# WalkMod_A0.net
KiCad netlist of a schematic drawn in Altium Designer
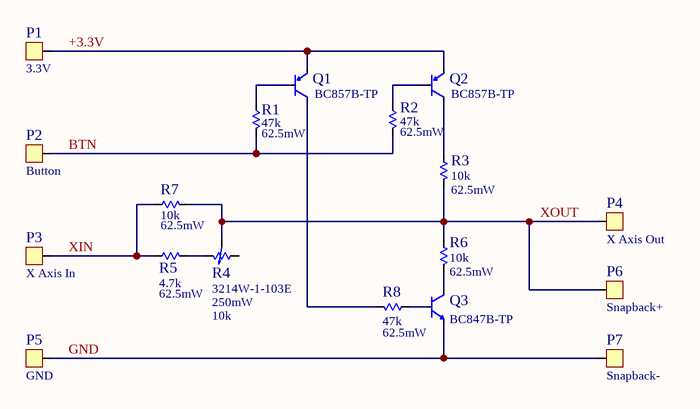
[diagram p0: WalkMod A0.SchDoc]

(export (version "E")
  (design (tool "Eeschema 10.0.6"))
  (components
    (comp (ref "P1")
      (value "SMD Pad 1 pin")
      (footprint "PAD_2X1.5_SQUARE")
      (description "Single SMD Pad")
      (fields (field (name "NAME") "3.3V"))
      (libsource (lib "WalkMod") (part "SMD Pad 1 pin"))
    )
    (comp (ref "P2")
      (value "SMD Pad 1 pin")
      (footprint "PAD_2X1.5_SQUARE")
      (description "Single SMD Pad")
      (fields (field (name "NAME") "Button"))
      (libsource (lib "WalkMod") (part "SMD Pad 1 pin"))
    )
    (comp (ref "P3")
      (value "SMD Pad 1 pin")
      (footprint "PAD_2X1.5_SQUARE")
      (description "Single SMD Pad")
      (fields (field (name "NAME") "X Axis In"))
      (libsource (lib "WalkMod") (part "SMD Pad 1 pin"))
    )
    (comp (ref "P4")
      (value "SMD Pad 1 pin")
      (footprint "PAD_2X1.5_SQUARE")
      (description "Single SMD Pad")
      (fields (field (name "NAME") "X Axis Out"))
      (libsource (lib "") (part "SMD Pad 1 pin_1"))
    )
    (comp (ref "P5")
      (value "SMD Pad 1 pin")
      (footprint "PAD_2X1.5_SQUARE")
      (description "Single SMD Pad")
      (fields (field (name "NAME") "GND"))
      (libsource (lib "WalkMod") (part "SMD Pad 1 pin"))
    )
    (comp (ref "P6")
      (value "SMD Pad 1 pin")
      (footprint "PAD_1.8X0.95_SQUARE")
      (description "Single SMD Pad")
      (fields (field (name "NAME") "Snapback+"))
      (libsource (lib "") (part "SMD Pad 1 pin_1"))
    )
    (comp (ref "P7")
      (value "SMD Pad 1 pin")
      (footprint "PAD_1.8X0.95_SQUARE")
      (description "Single SMD Pad")
      (fields (field (name "NAME") "Snapback-"))
      (libsource (lib "") (part "SMD Pad 1 pin_1"))
    )
    (comp (ref "Q1")
      (value "BC857B-TP")
      (footprint "BC8xx_SOT23-3_C")
      (description "Bipolar (BJT) Transistor PNP 45 V 100 mA 200MHz 310 mW Surface Mount SOT-23")
      (libsource (lib "WalkMod") (part "BC857B-TP"))
    )
    (comp (ref "Q2")
      (value "BC857B-TP")
      (footprint "BC8xx_SOT23-3_C")
      (description "Bipolar (BJT) Transistor PNP 45 V 100 mA 200MHz 310 mW Surface Mount SOT-23")
      (libsource (lib "WalkMod") (part "BC857B-TP"))
    )
    (comp (ref "Q3")
      (value "BC847B-TP")
      (footprint "BC8xx_SOT23-3_C")
      (description "Bipolar (BJT) Transistor NPN 45 V 100 mA 100MHz 225 mW Surface Mount SOT-23")
      (libsource (lib "WalkMod") (part "BC847B-TP"))
    )
    (comp (ref "R1")
      (value "47k")
      (footprint "RT0402_C")
      (description "47 kOhms ±0.5% 0.063W, 1/16W Chip Resistor 0402 (1005 Metric) - Thin Film")
      (fields (field (name "VALUE2") "62.5mW") (field (name "Comment") "RT0402DRD0747KL"))
      (libsource (lib "WalkMod") (part "RT0402DRD0747KL"))
    )
    (comp (ref "R2")
      (value "47k")
      (footprint "RT0402_C")
      (description "47 kOhms ±0.5% 0.063W, 1/16W Chip Resistor 0402 (1005 Metric) - Thin Film")
      (fields (field (name "VALUE2") "62.5mW") (field (name "Comment") "RT0402DRD0747KL"))
      (libsource (lib "WalkMod") (part "RT0402DRD0747KL"))
    )
    (comp (ref "R3")
      (value "10k")
      (footprint "AT0402_C")
      (fields (field (name "VALUE2") "62.5mW") (field (name "Comment") "AT0402FRE0710KL"))
      (libsource (lib "WalkMod") (part "AT0402FRE0710KL"))
    )
    (comp (ref "R4")
      (value "3214W-1-103E")
      (footprint "BOURNS_3214W_C")
      (description "10 kOhms 0.25W, 1/4W J Lead Surface Mount Trimmer Potentiometer Cermet 5.0 Turn Top Adjustment")
      (fields (field (name "VALUE2") "250mW") (field (name "ALTIUM_VALUE") "10k"))
      (libsource (lib "WalkMod") (part "3214W-1-103E"))
    )
    (comp (ref "R5")
      (value "4.7k")
      (footprint "RT0402_C")
      (description "4.7 kOhms ±1% 0.063W, 1/16W Chip Resistor 0402 (1005 Metric) - Thin Film")
      (fields (field (name "VALUE2") "62.5mW") (field (name "Comment") "RT0402FRE074K7L"))
      (libsource (lib "WalkMod") (part "RT0402FRE074K7L"))
    )
    (comp (ref "R6")
      (value "10k")
      (footprint "AT0402_C")
      (fields (field (name "VALUE2") "62.5mW") (field (name "Comment") "AT0402FRE0710KL"))
      (libsource (lib "WalkMod") (part "AT0402FRE0710KL"))
    )
    (comp (ref "R7")
      (value "10k")
      (footprint "AT0402_C")
      (fields (field (name "VALUE2") "62.5mW") (field (name "Comment") "AT0402FRE0710KL"))
      (libsource (lib "WalkMod") (part "AT0402FRE0710KL"))
    )
    (comp (ref "R8")
      (value "47k")
      (footprint "RT0402_C")
      (description "47 kOhms ±0.5% 0.063W, 1/16W Chip Resistor 0402 (1005 Metric) - Thin Film")
      (fields (field (name "VALUE2") "62.5mW") (field (name "Comment") "RT0402DRD0747KL"))
      (libsource (lib "WalkMod") (part "RT0402DRD0747KL"))
    )
  )
  (nets
    (net (code "1") (name "/+3.3V") (class "Default")
      (node (ref "P1") (pin "1") (pinfunction "1_1") (pintype "passive"))
      (node (ref "Q1") (pin "E") (pinfunction "E_E") (pintype "passive"))
      (node (ref "Q2") (pin "E") (pinfunction "E_E") (pintype "passive"))
    )
    (net (code "2") (name "/BTN") (class "Default")
      (node (ref "P2") (pin "1") (pinfunction "1_1") (pintype "passive"))
      (node (ref "R1") (pin "1") (pinfunction "1_1") (pintype "passive"))
      (node (ref "R2") (pin "1") (pinfunction "1_1") (pintype "passive"))
    )
    (net (code "3") (name "/GND") (class "Default")
      (node (ref "P5") (pin "1") (pinfunction "1_1") (pintype "passive"))
      (node (ref "P7") (pin "1") (pinfunction "1_1") (pintype "passive"))
      (node (ref "Q3") (pin "E") (pinfunction "E_E") (pintype "passive"))
    )
    (net (code "4") (name "/XIN") (class "Default")
      (node (ref "P3") (pin "1") (pinfunction "1_1") (pintype "passive"))
      (node (ref "R5") (pin "1") (pinfunction "1_1") (pintype "passive"))
      (node (ref "R7") (pin "2") (pinfunction "2_2") (pintype "passive"))
    )
    (net (code "5") (name "/XOUT") (class "Default")
      (node (ref "P4") (pin "1") (pinfunction "1_1") (pintype "passive"))
      (node (ref "P6") (pin "1") (pinfunction "1_1") (pintype "passive"))
      (node (ref "R3") (pin "2") (pinfunction "2_2") (pintype "passive"))
      (node (ref "R4") (pin "2") (pinfunction "2_2") (pintype "passive"))
      (node (ref "R6") (pin "1") (pinfunction "1_1") (pintype "passive"))
      (node (ref "R7") (pin "1") (pinfunction "1_1") (pintype "passive"))
    )
    (net (code "6") (name "Net-(Q1-PadB)") (class "Default")
      (node (ref "Q1") (pin "B") (pinfunction "B_B") (pintype "passive"))
      (node (ref "R1") (pin "2") (pinfunction "2_2") (pintype "passive"))
    )
    (net (code "7") (name "Net-(Q1-PadC)") (class "Default")
      (node (ref "Q1") (pin "C") (pinfunction "C_C") (pintype "passive"))
      (node (ref "R8") (pin "1") (pinfunction "1_1") (pintype "passive"))
    )
    (net (code "8") (name "Net-(Q2-PadB)") (class "Default")
      (node (ref "Q2") (pin "B") (pinfunction "B_B") (pintype "passive"))
      (node (ref "R2") (pin "2") (pinfunction "2_2") (pintype "passive"))
    )
    (net (code "9") (name "Net-(Q2-PadC)") (class "Default")
      (node (ref "Q2") (pin "C") (pinfunction "C_C") (pintype "passive"))
      (node (ref "R3") (pin "1") (pinfunction "1_1") (pintype "passive"))
    )
    (net (code "10") (name "Net-(Q3-PadB)") (class "Default")
      (node (ref "Q3") (pin "B") (pinfunction "B_B") (pintype "passive"))
      (node (ref "R8") (pin "2") (pinfunction "2_2") (pintype "passive"))
    )
    (net (code "11") (name "Net-(Q3-PadC)") (class "Default")
      (node (ref "Q3") (pin "C") (pinfunction "C_C") (pintype "passive"))
      (node (ref "R6") (pin "2") (pinfunction "2_2") (pintype "passive"))
    )
    (net (code "12") (name "Net-(R4-Pad3)") (class "Default")
      (node (ref "R4") (pin "3") (pinfunction "3_3") (pintype "passive"))
      (node (ref "R5") (pin "2") (pinfunction "2_2") (pintype "passive"))
    )
    (net (code "13") (name "unconnected-(R4-Pad1)") (class "Default")
      (node (ref "R4") (pin "1") (pinfunction "1_1") (pintype "passive"))
    )
  )
)
